# EEZ_PSU_post-regulator_r4B44.net
KiCad netlist of a schematic drawn in EAGLE
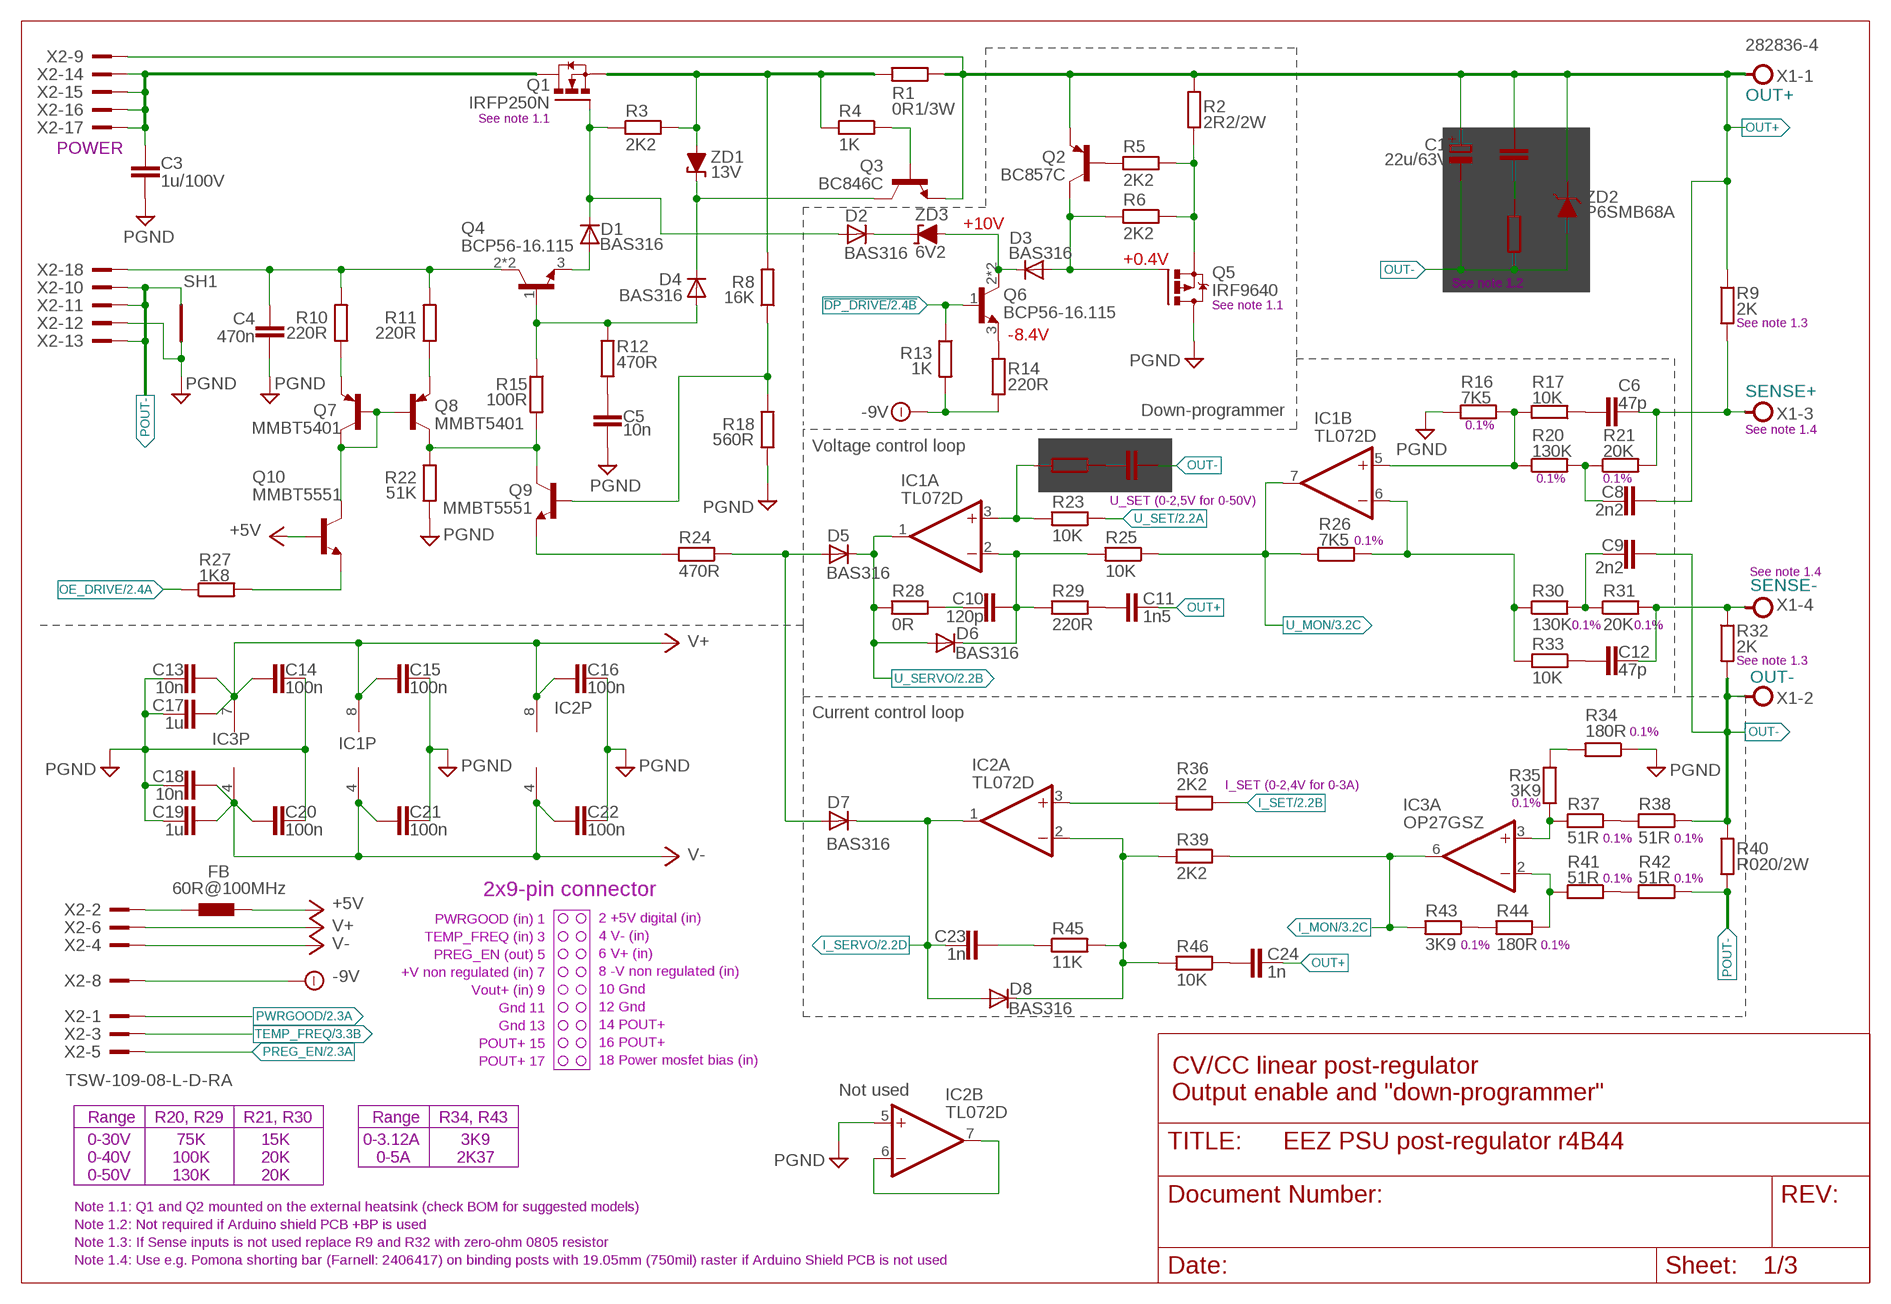
[diagram p0: schematic, sheet 1]
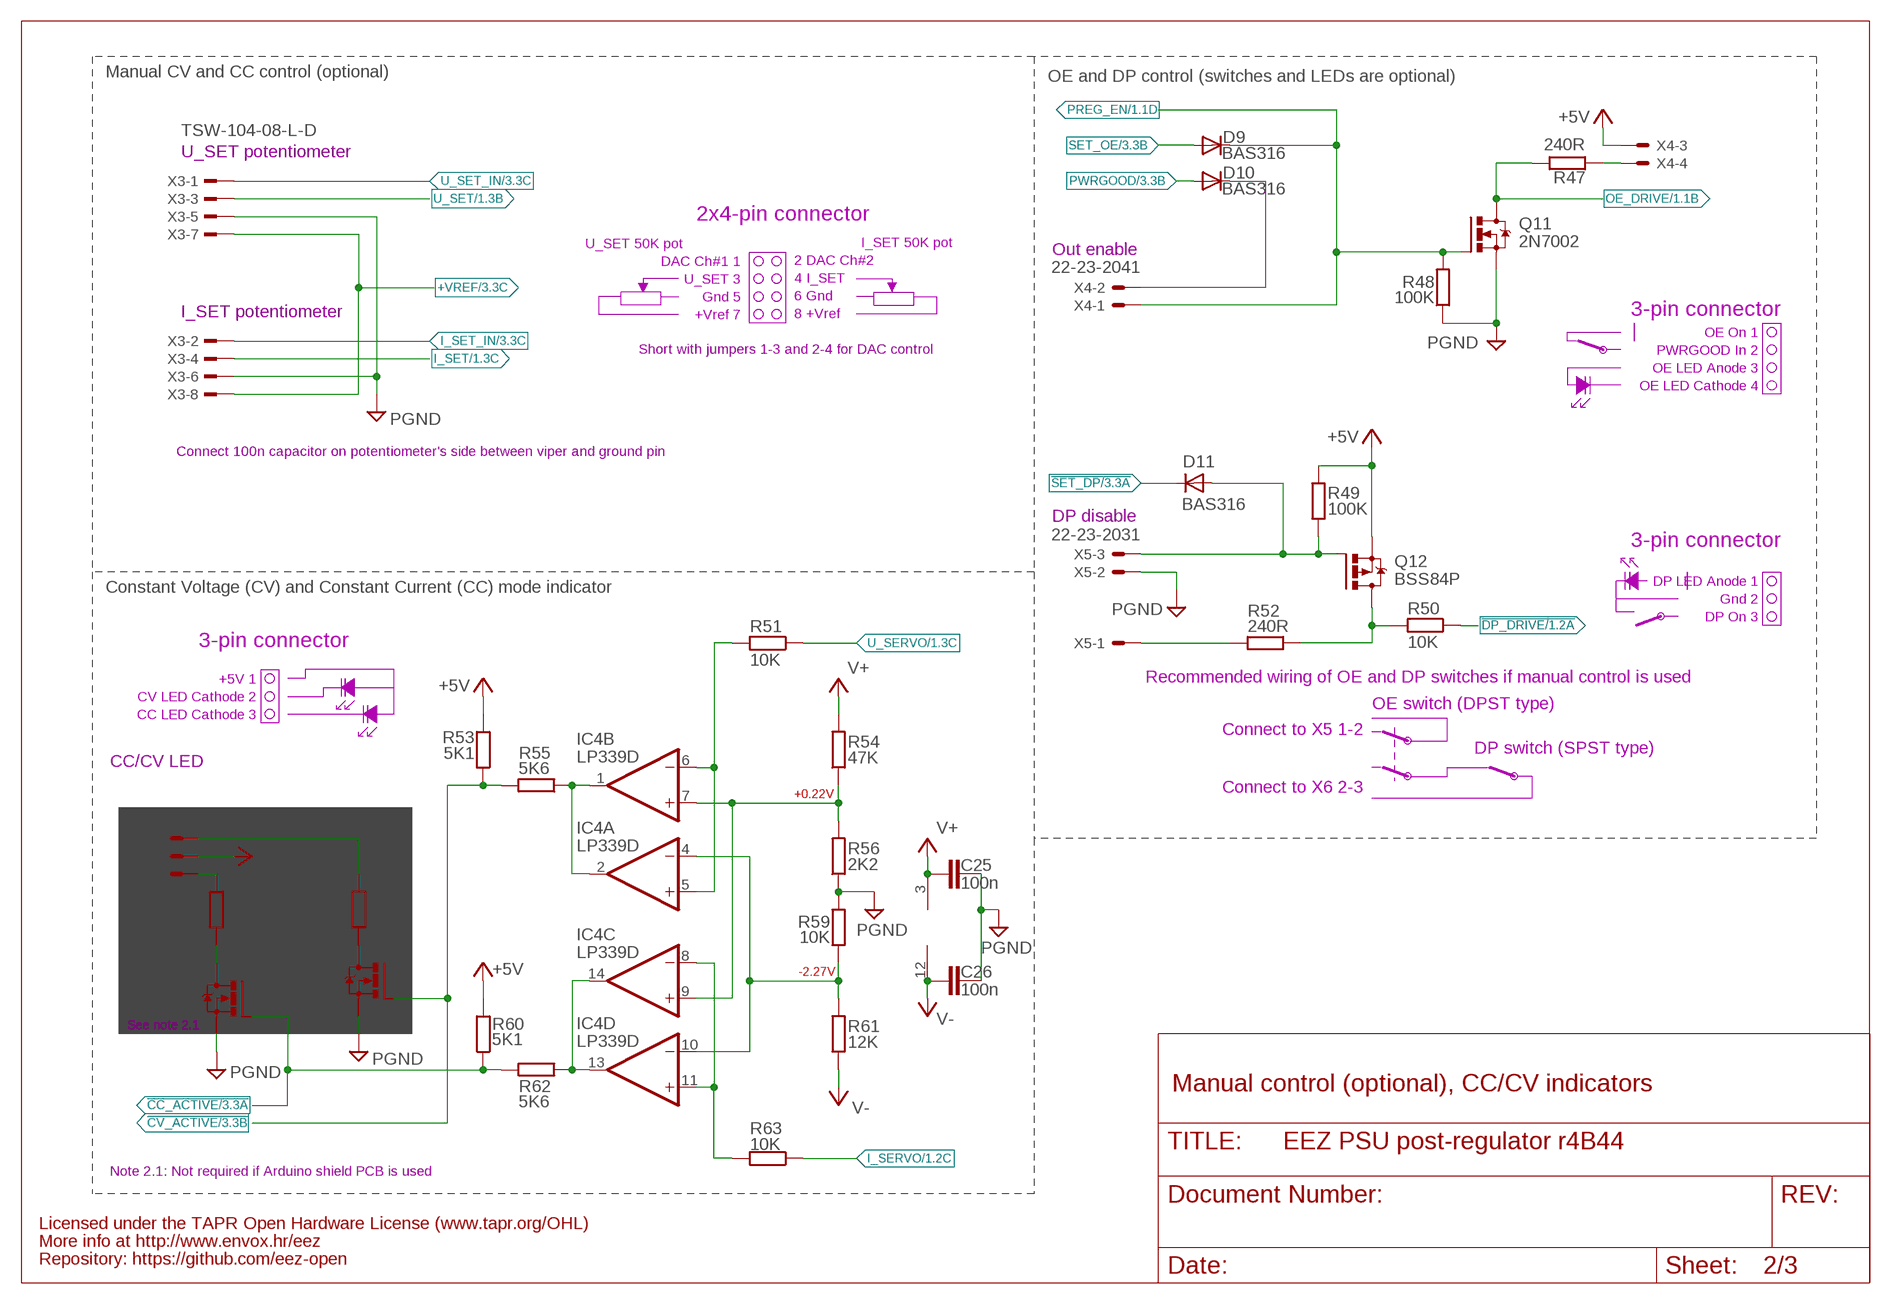
[diagram p1: schematic, sheet 2]
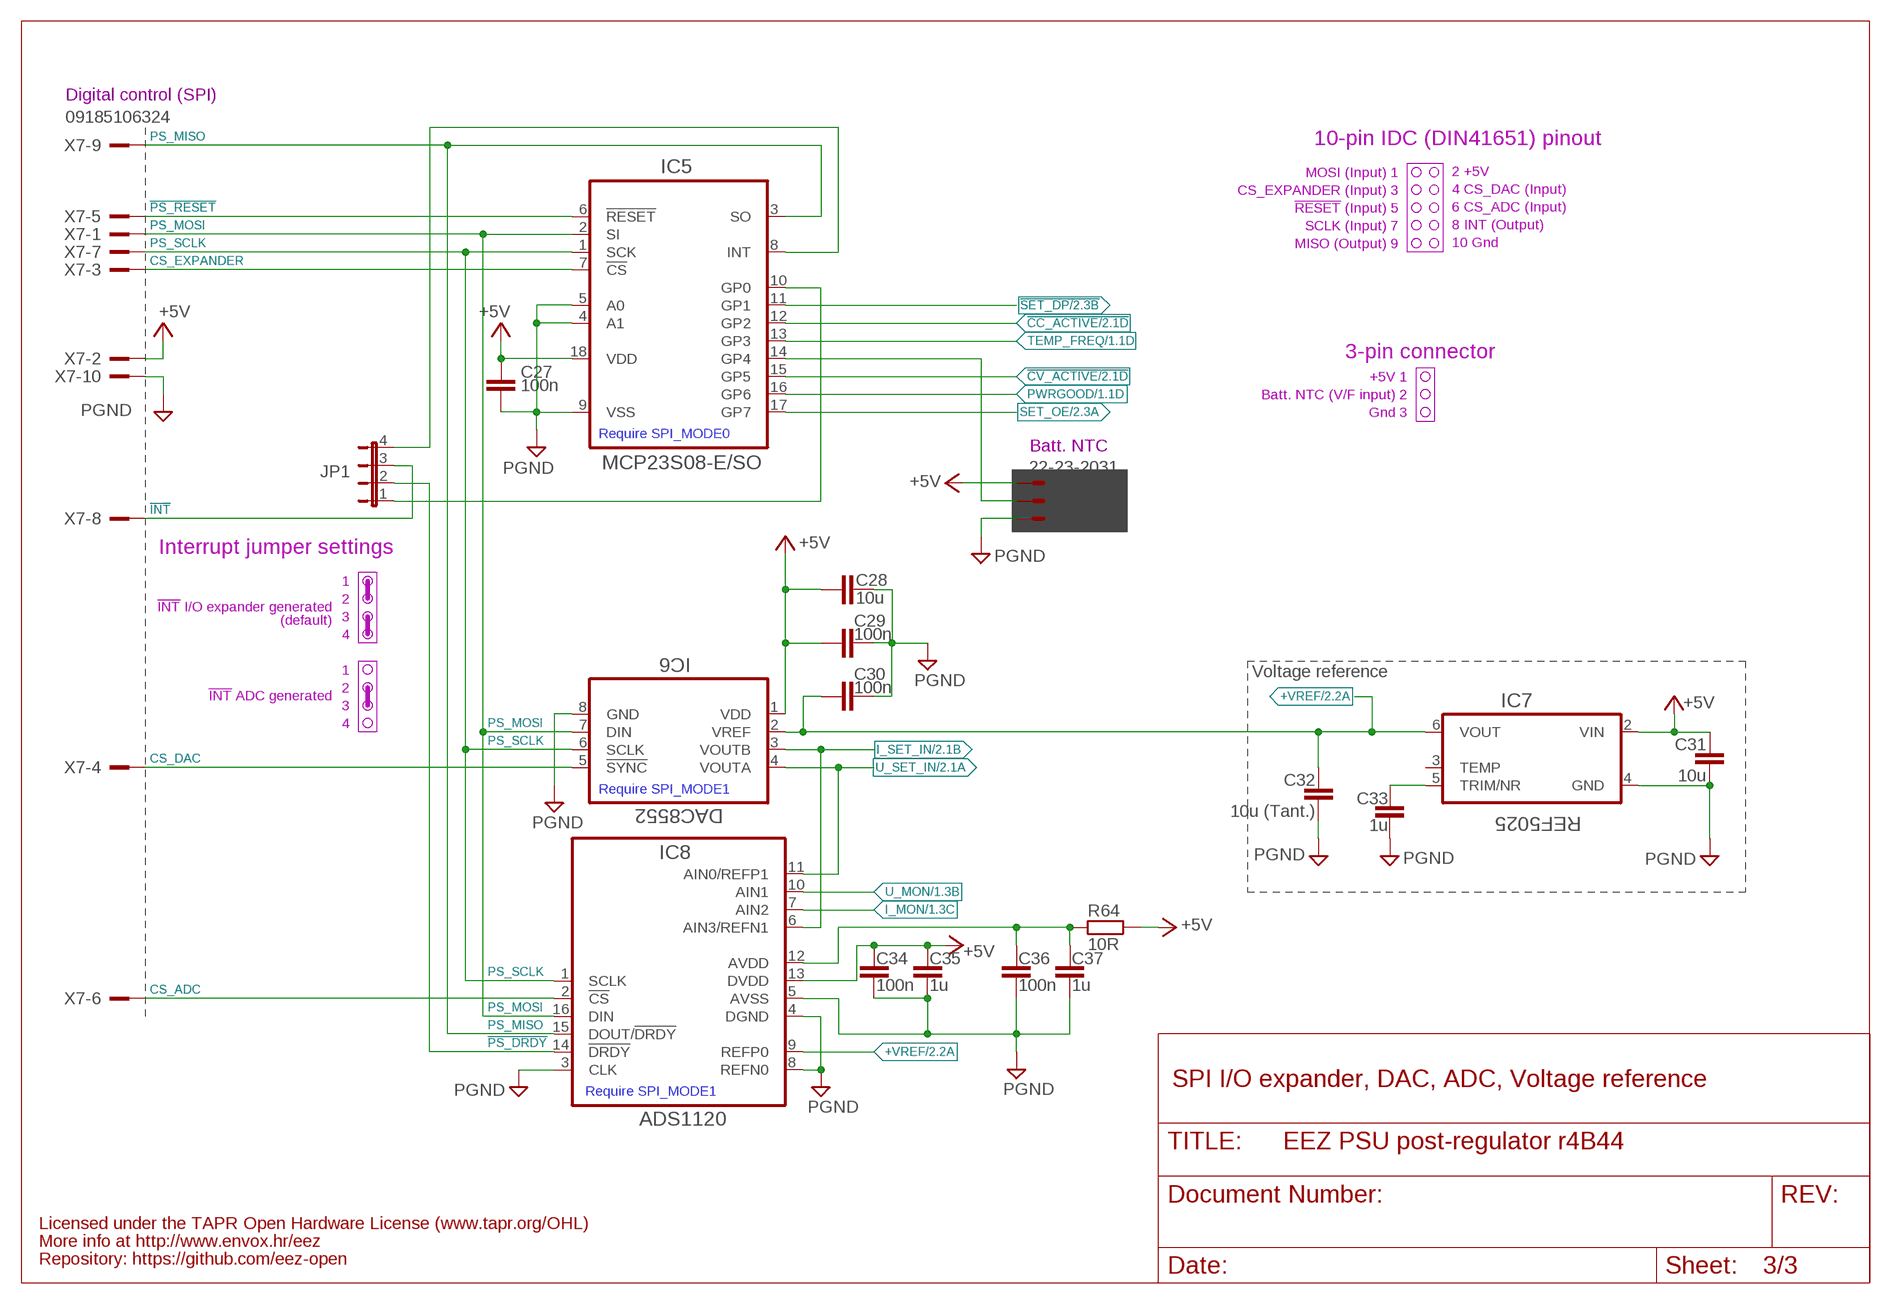
[diagram p2: schematic, sheet 3]

(export (version "E")
  (design (tool "Eeschema 10.0.6"))
  (components
    (comp (ref "C25")
      (value "100n")
      (footprint "eagle-import:C0603")
      (libsource (lib "eagle-import") (part "C-EUC0603"))
    )
    (comp (ref "C26")
      (value "100n")
      (footprint "eagle-import:C0603")
      (libsource (lib "eagle-import") (part "C-EUC0603"))
    )
    (comp (ref "D9")
      (value "BAS316")
      (footprint "eagle-import:SOD323-W")
      (libsource (lib "eagle-import") (part "DIODE-SOD323-W"))
    )
    (comp (ref "D10")
      (value "BAS316")
      (footprint "eagle-import:SOD323-W")
      (libsource (lib "eagle-import") (part "DIODE-SOD323-W"))
    )
    (comp (ref "D11")
      (value "BAS316")
      (footprint "eagle-import:SOD323-W")
      (libsource (lib "eagle-import") (part "DIODE-SOD323-W"))
    )
    (comp (ref "IC4")
      (value "LP339D")
      (footprint "eagle-import:SO14")
      (libsource (lib "eagle-import") (part "LM339D"))
    )
    (comp (ref "Q11")
      (value "2N7002")
      (footprint "eagle-import:SOT103P240X110-3N")
      (fields
        (field (name "MPN") "2N7002-7-F")
        (field (name "MPN_1") "2N7002-7-F")
        (field (name "OC_FARNELL") "1713823")
        (field (name "OC_NEWARK") "25R5679")
        (field (name "PACKAGE") "SOT-23-3")
        (field (name "SUPPLIER") "DIODES INC.")
      )
      (libsource (lib "eagle-import") (part "2N7002"))
    )
    (comp (ref "Q12")
      (value "BSS84P")
      (footprint "eagle-import:SOT95P237X112-3N")
      (fields (field (name "MPN") "IRLML2246TRPBF"))
      (libsource (lib "eagle-import") (part "IRLML2246TRPBF"))
    )
    (comp (ref "Q13")
      (value "2N7002")
      (footprint "eagle-import:SOT103P240X110-3N")
      (fields (field (name "MPN") "2N7002-7-F"))
      (libsource (lib "eagle-import") (part "2N7002"))
    )
    (comp (ref "Q14")
      (value "2N7002")
      (footprint "eagle-import:SOT103P240X110-3N")
      (fields (field (name "MPN") "2N7002-7-F"))
      (libsource (lib "eagle-import") (part "2N7002"))
    )
    (comp (ref "R47")
      (value "240R")
      (footprint "eagle-import:R0805")
      (libsource (lib "eagle-import") (part "R-EU_R0805"))
    )
    (comp (ref "R48")
      (value "100K")
      (footprint "eagle-import:R0805")
      (libsource (lib "eagle-import") (part "R-EU_R0805"))
    )
    (comp (ref "R49")
      (value "100K")
      (footprint "eagle-import:R0805")
      (libsource (lib "eagle-import") (part "R-EU_R0805"))
    )
    (comp (ref "R50")
      (value "10K")
      (footprint "eagle-import:R0805")
      (libsource (lib "eagle-import") (part "R-EU_R0805"))
    )
    (comp (ref "R51")
      (value "10K")
      (footprint "eagle-import:R0805")
      (libsource (lib "eagle-import") (part "R-EU_R0805"))
    )
    (comp (ref "R52")
      (value "240R")
      (footprint "eagle-import:R0805")
      (libsource (lib "eagle-import") (part "R-EU_R0805"))
    )
    (comp (ref "R53")
      (value "5K1")
      (footprint "eagle-import:R0805")
      (libsource (lib "eagle-import") (part "R-EU_R0805"))
    )
    (comp (ref "R54")
      (value "47K")
      (footprint "eagle-import:R0805")
      (libsource (lib "eagle-import") (part "R-EU_R0805"))
    )
    (comp (ref "R55")
      (value "5K6")
      (footprint "eagle-import:R0805")
      (libsource (lib "eagle-import") (part "R-EU_R0805"))
    )
    (comp (ref "R56")
      (value "2K2")
      (footprint "eagle-import:R0805")
      (libsource (lib "eagle-import") (part "R-EU_R0805"))
    )
    (comp (ref "R57")
      (value "240R")
      (footprint "eagle-import:R0805")
      (libsource (lib "eagle-import") (part "R-EU_R0805"))
    )
    (comp (ref "R58")
      (value "240R")
      (footprint "eagle-import:R0805")
      (libsource (lib "eagle-import") (part "R-EU_R0805"))
    )
    (comp (ref "R59")
      (value "10K")
      (footprint "eagle-import:R0805")
      (libsource (lib "eagle-import") (part "R-EU_R0805"))
    )
    (comp (ref "R60")
      (value "5K1")
      (footprint "eagle-import:R0805")
      (libsource (lib "eagle-import") (part "R-EU_R0805"))
    )
    (comp (ref "R61")
      (value "12K")
      (footprint "eagle-import:R0805")
      (libsource (lib "eagle-import") (part "R-EU_R0805"))
    )
    (comp (ref "R62")
      (value "5K6")
      (footprint "eagle-import:R0805")
      (libsource (lib "eagle-import") (part "R-EU_R0805"))
    )
    (comp (ref "R63")
      (value "10K")
      (footprint "eagle-import:R0805")
      (libsource (lib "eagle-import") (part "R-EU_R0805"))
    )
    (comp (ref "X3")
      (value "TSW-104-08-L-D")
      (footprint "eagle-import:TSW-104-02-S-D")
      (libsource (lib "eagle-import") (part "TSW-104-02-S-D"))
    )
    (comp (ref "X4")
      (value "22-23-2041")
      (footprint "eagle-import:22-23-2041")
      (fields
        (field (name "MF") "MOLEX")
        (field (name "MPN") "22-23-2041")
        (field (name "OC_FARNELL") "1462920")
        (field (name "OC_NEWARK") "38C0355")
      )
      (libsource (lib "eagle-import") (part "22-23-2041"))
    )
    (comp (ref "X5")
      (value "22-23-2031")
      (footprint "eagle-import:22-23-2031")
      (fields
        (field (name "MF") "MOLEX")
        (field (name "MF_1") "MOLEX")
        (field (name "MPN") "22-23-2031")
        (field (name "OC_FARNELL") "1462950")
        (field (name "OC_NEWARK") "30C0862")
      )
      (libsource (lib "eagle-import") (part "22-23-2031"))
    )
    (comp (ref "X6")
      (value "22-23-2031")
      (footprint "eagle-import:22-23-2031")
      (fields
        (field (name "MF") "MOLEX")
        (field (name "MPN") "22-23-2031")
        (field (name "OC_FARNELL") "1462950")
        (field (name "OC_NEWARK") "30C0862")
      )
      (libsource (lib "eagle-import") (part "22-23-2031"))
    )
    (comp (ref "C1")
      (value "22u/63V")
      (footprint "eagle-import:CAPAE660X610N_COMBO2")
      (libsource (lib "eagle-import") (part "ECAPEEEFK+2.5MM"))
    )
    (comp (ref "C2")
      (value "470n")
      (footprint "eagle-import:C1812")
      (libsource (lib "eagle-import") (part "C-EUC1812"))
    )
    (comp (ref "C3")
      (value "1u/100V")
      (footprint "eagle-import:C1206")
      (libsource (lib "eagle-import") (part "C-EUC1206"))
    )
    (comp (ref "C4")
      (value "470n")
      (footprint "eagle-import:C1812")
      (libsource (lib "eagle-import") (part "C-EUC1812"))
    )
    (comp (ref "C5")
      (value "10n")
      (footprint "eagle-import:C0805")
      (libsource (lib "eagle-import") (part "C-EUC0805"))
    )
    (comp (ref "C6")
      (value "47p")
      (footprint "eagle-import:C0805")
      (libsource (lib "eagle-import") (part "C-EUC0805"))
    )
    (comp (ref "C7")
      (value "1n5")
      (footprint "eagle-import:C0805")
      (libsource (lib "eagle-import") (part "C-EUC0805"))
    )
    (comp (ref "C8")
      (value "2n2")
      (footprint "eagle-import:C0805")
      (libsource (lib "eagle-import") (part "C-EUC0805"))
    )
    (comp (ref "C9")
      (value "2n2")
      (footprint "eagle-import:C0805")
      (libsource (lib "eagle-import") (part "C-EUC0805"))
    )
    (comp (ref "C10")
      (value "120p")
      (footprint "eagle-import:C0805")
      (libsource (lib "eagle-import") (part "C-EUC0805"))
    )
    (comp (ref "C11")
      (value "1n5")
      (footprint "eagle-import:C0805")
      (libsource (lib "eagle-import") (part "C-EUC0805"))
    )
    (comp (ref "C12")
      (value "47p")
      (footprint "eagle-import:C0805")
      (libsource (lib "eagle-import") (part "C-EUC0805"))
    )
    (comp (ref "C13")
      (value "10n")
      (footprint "eagle-import:C0805")
      (libsource (lib "eagle-import") (part "C-EUC0805"))
    )
    (comp (ref "C14")
      (value "100n")
      (footprint "eagle-import:C0603")
      (libsource (lib "eagle-import") (part "C-EUC0603"))
    )
    (comp (ref "C15")
      (value "100n")
      (footprint "eagle-import:C0603")
      (libsource (lib "eagle-import") (part "C-EUC0603"))
    )
    (comp (ref "C16")
      (value "100n")
      (footprint "eagle-import:C0603")
      (libsource (lib "eagle-import") (part "C-EUC0603"))
    )
    (comp (ref "C17")
      (value "1u")
      (footprint "eagle-import:C0805")
      (libsource (lib "eagle-import") (part "C-EUC0805"))
    )
    (comp (ref "C18")
      (value "10n")
      (footprint "eagle-import:C0805")
      (libsource (lib "eagle-import") (part "C-EUC0805"))
    )
    (comp (ref "C19")
      (value "1u")
      (footprint "eagle-import:C0805")
      (libsource (lib "eagle-import") (part "C-EUC0805"))
    )
    (comp (ref "C20")
      (value "100n")
      (footprint "eagle-import:C0603")
      (libsource (lib "eagle-import") (part "C-EUC0603"))
    )
    (comp (ref "C21")
      (value "100n")
      (footprint "eagle-import:C0603")
      (libsource (lib "eagle-import") (part "C-EUC0603"))
    )
    (comp (ref "C22")
      (value "100n")
      (footprint "eagle-import:C0603")
      (libsource (lib "eagle-import") (part "C-EUC0603"))
    )
    (comp (ref "C23")
      (value "1n")
      (footprint "eagle-import:C0805")
      (libsource (lib "eagle-import") (part "C-EUC0805"))
    )
    (comp (ref "C24")
      (value "1n")
      (footprint "eagle-import:C0805")
      (libsource (lib "eagle-import") (part "C-EUC0805"))
    )
    (comp (ref "D1")
      (value "BAS316")
      (footprint "eagle-import:SOD323-W")
      (libsource (lib "eagle-import") (part "DIODE-SOD323-W"))
    )
    (comp (ref "D2")
      (value "BAS316")
      (footprint "eagle-import:SOD323-W")
      (libsource (lib "eagle-import") (part "DIODE-SOD323-W"))
    )
    (comp (ref "D3")
      (value "BAS316")
      (footprint "eagle-import:SOD323-W")
      (libsource (lib "eagle-import") (part "DIODE-SOD323-W"))
    )
    (comp (ref "D4")
      (value "BAS316")
      (footprint "eagle-import:SOD323-W")
      (libsource (lib "eagle-import") (part "DIODE-SOD323-W"))
    )
    (comp (ref "D5")
      (value "BAS316")
      (footprint "eagle-import:SOD323-W")
      (libsource (lib "eagle-import") (part "DIODE-SOD323-W"))
    )
    (comp (ref "D6")
      (value "BAS316")
      (footprint "eagle-import:SOD323-W")
      (libsource (lib "eagle-import") (part "DIODE-SOD323-W"))
    )
    (comp (ref "D7")
      (value "BAS316")
      (footprint "eagle-import:SOD323-W")
      (libsource (lib "eagle-import") (part "DIODE-SOD323-W"))
    )
    (comp (ref "D8")
      (value "BAS316")
      (footprint "eagle-import:SOD323-W")
      (libsource (lib "eagle-import") (part "DIODE-SOD323-W"))
    )
    (comp (ref "FB")
      (value "60R@100MHz")
      (footprint "eagle-import:BEAD0603")
      (libsource (lib "eagle-import") (part "FERRITE_BEAD0603"))
    )
    (comp (ref "IC1")
      (value "TL072D")
      (footprint "eagle-import:SOIC127P600X173-8N")
      (libsource (lib "eagle-import") (part "TL072SOIC8"))
    )
    (comp (ref "IC2")
      (value "TL072D")
      (footprint "eagle-import:SOIC127P600X173-8N")
      (libsource (lib "eagle-import") (part "TL072SOIC8"))
    )
    (comp (ref "IC3")
      (value "OP27GSZ")
      (footprint "eagle-import:SOIC127P600X173-8N")
      (libsource (lib "eagle-import") (part "OP27GSZSO8"))
    )
    (comp (ref "Q1")
      (value "IRFP250N")
      (footprint "eagle-import:TO247BV")
      (libsource (lib "eagle-import") (part "IRFP240"))
    )
    (comp (ref "Q2")
      (value "BC857C")
      (footprint "eagle-import:SOT23-BEC")
      (libsource (lib "eagle-import") (part "-PNP-SOT23-BECBC857C"))
    )
    (comp (ref "Q3")
      (value "BC846C")
      (footprint "eagle-import:SOT23-BEC")
      (libsource (lib "eagle-import") (part "-NPN-SOT23-BECBC846B"))
    )
    (comp (ref "Q4")
      (value "BCP56-16.115")
      (footprint "eagle-import:SOT230P700X180-4N")
      (libsource (lib "eagle-import") (part "BCP56"))
    )
    (comp (ref "Q5")
      (value "IRF9640")
      (footprint "eagle-import:TO220B-VMOS")
      (libsource (lib "eagle-import") (part "IRF9640"))
    )
    (comp (ref "Q6")
      (value "BCP56-16.115")
      (footprint "eagle-import:SOT230P700X180-4N")
      (libsource (lib "eagle-import") (part "BCP56"))
    )
    (comp (ref "Q7")
      (value "MMBT5401")
      (footprint "eagle-import:SOT23-BEC")
      (libsource (lib "eagle-import") (part "-PNP-SOT23-BECBC857B"))
    )
    (comp (ref "Q8")
      (value "MMBT5401")
      (footprint "eagle-import:SOT23-BEC")
      (libsource (lib "eagle-import") (part "-PNP-SOT23-BECBC857B"))
    )
    (comp (ref "Q9")
      (value "MMBT5551")
      (footprint "eagle-import:SOT23-BEC")
      (libsource (lib "eagle-import") (part "-NPN-SOT23-BECMMBT5551LT1"))
    )
    (comp (ref "Q10")
      (value "MMBT5551")
      (footprint "eagle-import:SOT23-BEC")
      (libsource (lib "eagle-import") (part "-NPN-SOT23-BECMMBT5551LT1"))
    )
    (comp (ref "R1")
      (value "0R1/3W")
      (footprint "eagle-import:0411V")
      (libsource (lib "eagle-import") (part "R-EU_0411/3V"))
    )
    (comp (ref "R2")
      (value "2R2/2W")
      (footprint "eagle-import:0411V")
      (libsource (lib "eagle-import") (part "R-EU_0411/3V"))
    )
    (comp (ref "R3")
      (value "2K2")
      (footprint "eagle-import:R0805")
      (libsource (lib "eagle-import") (part "R-EU_R0805"))
    )
    (comp (ref "R4")
      (value "1K")
      (footprint "eagle-import:R0805")
      (libsource (lib "eagle-import") (part "R-EU_R0805"))
    )
    (comp (ref "R5")
      (value "2K2")
      (footprint "eagle-import:R0805")
      (libsource (lib "eagle-import") (part "R-EU_R0805"))
    )
    (comp (ref "R6")
      (value "2K2")
      (footprint "eagle-import:R0805")
      (libsource (lib "eagle-import") (part "R-EU_R0805"))
    )
    (comp (ref "R7")
      (value "1R")
      (footprint "eagle-import:R0805")
      (libsource (lib "eagle-import") (part "R-EU_R0805"))
    )
    (comp (ref "R8")
      (value "16K")
      (footprint "eagle-import:R0805")
      (libsource (lib "eagle-import") (part "R-EU_R0805"))
    )
    (comp (ref "R9")
      (value "2K")
      (footprint "eagle-import:R0805")
      (libsource (lib "eagle-import") (part "R-EU_R0805"))
    )
    (comp (ref "R10")
      (value "220R")
      (footprint "eagle-import:R0805")
      (libsource (lib "eagle-import") (part "R-EU_R0805"))
    )
    (comp (ref "R11")
      (value "220R")
      (footprint "eagle-import:R0805")
      (libsource (lib "eagle-import") (part "R-EU_R0805"))
    )
    (comp (ref "R12")
      (value "470R")
      (footprint "eagle-import:R0805")
      (libsource (lib "eagle-import") (part "R-EU_R0805"))
    )
    (comp (ref "R13")
      (value "1K")
      (footprint "eagle-import:R0805")
      (libsource (lib "eagle-import") (part "R-EU_R0805"))
    )
    (comp (ref "R14")
      (value "220R")
      (footprint "eagle-import:R0805")
      (libsource (lib "eagle-import") (part "R-EU_R0805"))
    )
    (comp (ref "R15")
      (value "100R")
      (footprint "eagle-import:R0805")
      (libsource (lib "eagle-import") (part "R-EU_R0805"))
    )
    (comp (ref "R16")
      (value "7K5")
      (footprint "eagle-import:R0805")
      (libsource (lib "eagle-import") (part "R-EU_R0805"))
    )
    (comp (ref "R17")
      (value "10K")
      (footprint "eagle-import:R0805")
      (libsource (lib "eagle-import") (part "R-EU_R0805"))
    )
    (comp (ref "R18")
      (value "560R")
      (footprint "eagle-import:R0805")
      (libsource (lib "eagle-import") (part "R-EU_R0805"))
    )
    (comp (ref "R19")
      (value "220R")
      (footprint "eagle-import:R0805")
      (libsource (lib "eagle-import") (part "R-EU_R0805"))
    )
    (comp (ref "R20")
      (value "130K")
      (footprint "eagle-import:R0805")
      (libsource (lib "eagle-import") (part "R-EU_R0805"))
    )
    (comp (ref "R21")
      (value "20K")
      (footprint "eagle-import:R0805")
      (libsource (lib "eagle-import") (part "R-EU_R0805"))
    )
    (comp (ref "R22")
      (value "51K")
      (footprint "eagle-import:R0805")
      (libsource (lib "eagle-import") (part "R-EU_R0805"))
    )
    (comp (ref "R23")
      (value "10K")
      (footprint "eagle-import:R0805")
      (libsource (lib "eagle-import") (part "R-EU_R0805"))
    )
    (comp (ref "R24")
      (value "470R")
      (footprint "eagle-import:R0805")
      (libsource (lib "eagle-import") (part "R-EU_R0805"))
    )
    (comp (ref "R25")
      (value "10K")
      (footprint "eagle-import:R0805")
      (libsource (lib "eagle-import") (part "R-EU_R0805"))
    )
    (comp (ref "R26")
      (value "7K5")
      (footprint "eagle-import:R0805")
      (libsource (lib "eagle-import") (part "R-EU_R0805"))
    )
    (comp (ref "R27")
      (value "1K8")
      (footprint "eagle-import:R0805")
      (libsource (lib "eagle-import") (part "R-EU_R0805"))
    )
    (comp (ref "R28")
      (value "0R")
      (footprint "eagle-import:R0805")
      (libsource (lib "eagle-import") (part "R-EU_R0805"))
    )
    (comp (ref "R29")
      (value "220R")
      (footprint "eagle-import:R0805")
      (libsource (lib "eagle-import") (part "R-EU_R0805"))
    )
    (comp (ref "R30")
      (value "130K")
      (footprint "eagle-import:R0805")
      (libsource (lib "eagle-import") (part "R-EU_R0805"))
    )
    (comp (ref "R31")
      (value "20K")
      (footprint "eagle-import:R0805")
      (libsource (lib "eagle-import") (part "R-EU_R0805"))
    )
    (comp (ref "R32")
      (value "2K")
      (footprint "eagle-import:R0805")
      (libsource (lib "eagle-import") (part "R-EU_R0805"))
    )
    (comp (ref "R33")
      (value "10K")
      (footprint "eagle-import:R0805")
      (libsource (lib "eagle-import") (part "R-EU_R0805"))
    )
    (comp (ref "R34")
      (value "180R")
      (footprint "eagle-import:R0805")
      (libsource (lib "eagle-import") (part "R-EU_R0805"))
    )
    (comp (ref "R35")
      (value "3K9")
      (footprint "eagle-import:R0805")
      (libsource (lib "eagle-import") (part "R-EU_R0805"))
    )
    (comp (ref "R36")
      (value "2K2")
      (footprint "eagle-import:R0805")
      (libsource (lib "eagle-import") (part "R-EU_R0805"))
    )
    (comp (ref "R37")
      (value "51R")
      (footprint "eagle-import:R0805")
      (libsource (lib "eagle-import") (part "R-EU_R0805"))
    )
    (comp (ref "R38")
      (value "51R")
      (footprint "eagle-import:R0805")
      (libsource (lib "eagle-import") (part "R-EU_R0805"))
    )
    (comp (ref "R39")
      (value "2K2")
      (footprint "eagle-import:R0805")
      (libsource (lib "eagle-import") (part "R-EU_R0805"))
    )
    (comp (ref "R40")
      (value "R020/2W")
      (footprint "eagle-import:R2512")
      (libsource (lib "eagle-import") (part "R-EU_R2512"))
    )
    (comp (ref "R41")
      (value "51R")
      (footprint "eagle-import:R0805")
      (libsource (lib "eagle-import") (part "R-EU_R0805"))
    )
    (comp (ref "R42")
      (value "51R")
      (footprint "eagle-import:R0805")
      (libsource (lib "eagle-import") (part "R-EU_R0805"))
    )
    (comp (ref "R43")
      (value "3K9")
      (footprint "eagle-import:R0805")
      (libsource (lib "eagle-import") (part "R-EU_R0805"))
    )
    (comp (ref "R44")
      (value "180R")
      (footprint "eagle-import:R0805")
      (libsource (lib "eagle-import") (part "R-EU_R0805"))
    )
    (comp (ref "R45")
      (value "11K")
      (footprint "eagle-import:R0805")
      (libsource (lib "eagle-import") (part "R-EU_R0805"))
    )
    (comp (ref "R46")
      (value "10K")
      (footprint "eagle-import:R0805")
      (libsource (lib "eagle-import") (part "R-EU_R0805"))
    )
    (comp (ref "SH1")
      (value "GND")
      (footprint "eagle-import:SHORT")
      (libsource (lib "eagle-import") (part "SHORT"))
    )
    (comp (ref "X1")
      (value "282836-4")
      (footprint "eagle-import:TBLOCK5.0_4")
      (libsource (lib "eagle-import") (part "TBLOCK5.0_4A"))
    )
    (comp (ref "X2")
      (value "TSW-109-08-L-D-RA")
      (footprint "eagle-import:TSW-109-08-L-D-RA")
      (fields (field (name "FARNELL") "2032801"))
      (libsource (lib "eagle-import") (part "TSW-109-08-L-D-RA"))
    )
    (comp (ref "ZD1")
      (value "13V")
      (footprint "eagle-import:MINIMELF")
      (libsource (lib "eagle-import") (part "ZENER-DIODEMINIMELF"))
    )
    (comp (ref "ZD2")
      (value "P6SMB68A")
      (footprint "eagle-import:DO214AA")
      (libsource (lib "eagle-import") (part "P6SMB68A"))
    )
    (comp (ref "ZD3")
      (value "6V2")
      (footprint "eagle-import:MINIMELF")
      (libsource (lib "eagle-import") (part "ZENER-DIODEMINIMELF"))
    )
    (comp (ref "C27")
      (value "100n")
      (footprint "eagle-import:C0603")
      (libsource (lib "eagle-import") (part "C-EUC0603"))
    )
    (comp (ref "C28")
      (value "10u")
      (footprint "eagle-import:C1206")
      (libsource (lib "eagle-import") (part "C-EUC1206"))
    )
    (comp (ref "C29")
      (value "100n")
      (footprint "eagle-import:C0603")
      (libsource (lib "eagle-import") (part "C-EUC0603"))
    )
    (comp (ref "C30")
      (value "100n")
      (footprint "eagle-import:C0603")
      (libsource (lib "eagle-import") (part "C-EUC0603"))
    )
    (comp (ref "C31")
      (value "10u")
      (footprint "eagle-import:C1206")
      (libsource (lib "eagle-import") (part "C-EUC1206"))
    )
    (comp (ref "C32")
      (value "10u (Tant.)")
      (footprint "eagle-import:C1206")
      (libsource (lib "eagle-import") (part "C-EUC1206"))
    )
    (comp (ref "C33")
      (value "1u")
      (footprint "eagle-import:C0805")
      (libsource (lib "eagle-import") (part "C-EUC0805"))
    )
    (comp (ref "C34")
      (value "100n")
      (footprint "eagle-import:C0603")
      (libsource (lib "eagle-import") (part "C-EUC0603"))
    )
    (comp (ref "C35")
      (value "1u")
      (footprint "eagle-import:C0805")
      (libsource (lib "eagle-import") (part "C-EUC0805"))
    )
    (comp (ref "C36")
      (value "100n")
      (footprint "eagle-import:C0603")
      (libsource (lib "eagle-import") (part "C-EUC0603"))
    )
    (comp (ref "C37")
      (value "1u")
      (footprint "eagle-import:C0805")
      (libsource (lib "eagle-import") (part "C-EUC0805"))
    )
    (comp (ref "IC5")
      (value "MCP23S08-E/SO")
      (footprint "eagle-import:SOIC127P1030X265-18N")
      (libsource (lib "eagle-import") (part "MCP23S08"))
    )
    (comp (ref "IC6")
      (value "DAC8552")
      (footprint "eagle-import:DGK8-M")
      (libsource (lib "eagle-import") (part "DAC8552_DGK_8M"))
    )
    (comp (ref "IC7")
      (value "REF5025")
      (footprint "eagle-import:SOIC127P600X175-8N")
      (libsource (lib "eagle-import") (part "REF50XX"))
    )
    (comp (ref "IC8")
      (value "ADS1120")
      (footprint "eagle-import:PW(R-PDSO-G16)")
      (libsource (lib "eagle-import") (part "ADS1120TSSOP-16"))
    )
    (comp (ref "JP1")
      (value "JP4E")
      (footprint "eagle-import:JP4")
      (libsource (lib "eagle-import") (part "JP4E"))
    )
    (comp (ref "R64")
      (value "10R")
      (footprint "eagle-import:R0805")
      (libsource (lib "eagle-import") (part "R-EU_R0805"))
    )
    (comp (ref "X7")
      (value "09185106324")
      (footprint "eagle-import:PAK100_2500-10")
      (fields (field (name "MF") "3M") (field (name "MPN") "2510-6002UB"))
      (libsource (lib "eagle-import") (part "2510-"))
    )
    (comp (ref "X8")
      (value "22-23-2031")
      (footprint "eagle-import:22-23-2031")
      (fields
        (field (name "MF") "MOLEX")
        (field (name "MPN") "22-23-2031")
        (field (name "OC_FARNELL") "1462950")
        (field (name "OC_NEWARK") "30C0862")
      )
      (libsource (lib "eagle-import") (part "22-23-2031"))
    )
  )
  (nets
    (net (code "1") (name "+5V") (class "Default")
      (node (ref "C27") (pin "1") (pinfunction "1_1") (pintype "passive"))
      (node (ref "C28") (pin "1") (pinfunction "1_1") (pintype "passive"))
      (node (ref "C29") (pin "2") (pinfunction "2_2") (pintype "passive"))
      (node (ref "C31") (pin "1") (pinfunction "1_1") (pintype "passive"))
      (node (ref "C34") (pin "2") (pinfunction "2_2") (pintype "passive"))
      (node (ref "C35") (pin "2") (pinfunction "2_2") (pintype "passive"))
      (node (ref "FB") (pin "P$2") (pinfunction "2_P$2") (pintype "passive"))
      (node (ref "IC5") (pin "18") (pinfunction "VDD_18") (pintype "power_in"))
      (node (ref "IC6") (pin "1") (pinfunction "VDD_1") (pintype "power_in"))
      (node (ref "IC7") (pin "2") (pinfunction "VIN_2") (pintype "passive"))
      (node (ref "IC8") (pin "13") (pinfunction "DVDD_13") (pintype "power_in"))
      (node (ref "Q10") (pin "B") (pinfunction "B_B") (pintype "passive"))
      (node (ref "Q12") (pin "2") (pinfunction "S_2") (pintype "passive"))
      (node (ref "R49") (pin "1") (pinfunction "1_1") (pintype "passive"))
      (node (ref "R53") (pin "2") (pinfunction "2_2") (pintype "passive"))
      (node (ref "R60") (pin "2") (pinfunction "2_2") (pintype "passive"))
      (node (ref "R64") (pin "1") (pinfunction "1_1") (pintype "passive"))
      (node (ref "X4") (pin "3") (pinfunction "S_3") (pintype "passive"))
      (node (ref "X6") (pin "2") (pinfunction "S_2") (pintype "passive"))
      (node (ref "X7") (pin "2") (pinfunction "KL_2") (pintype "passive"))
      (node (ref "X8") (pin "1") (pinfunction "S_1") (pintype "passive"))
    )
    (net (code "2") (name "+VREF") (class "Default")
      (node (ref "C30") (pin "2") (pinfunction "2_2") (pintype "passive"))
      (node (ref "C32") (pin "1") (pinfunction "1_1") (pintype "passive"))
      (node (ref "IC6") (pin "2") (pinfunction "VREF_2") (pintype "input"))
      (node (ref "IC7") (pin "6") (pinfunction "VOUT_6") (pintype "output"))
      (node (ref "IC8") (pin "9") (pinfunction "REFP0_9") (pintype "input"))
      (node (ref "X3") (pin "7") (pinfunction "1_7") (pintype "passive"))
      (node (ref "X3") (pin "8") (pinfunction "1_8") (pintype "passive"))
    )
    (net (code "3") (name "-9V") (class "Default")
      (node (ref "R13") (pin "2") (pinfunction "2_2") (pintype "passive"))
      (node (ref "R14") (pin "2") (pinfunction "2_2") (pintype "passive"))
      (node (ref "X2") (pin "8") (pinfunction "KL_8") (pintype "passive"))
    )
    (net (code "4") (name "CS_ADC") (class "Default")
      (node (ref "IC8") (pin "2") (pinfunction "~{CS}_2") (pintype "input"))
      (node (ref "X7") (pin "6") (pinfunction "KL_6") (pintype "passive"))
    )
    (net (code "5") (name "CS_DAC") (class "Default")
      (node (ref "IC6") (pin "5") (pinfunction "~{SYNC}_5") (pintype "input"))
      (node (ref "X7") (pin "4") (pinfunction "KL_4") (pintype "passive"))
    )
    (net (code "6") (name "CS_EXPANDER") (class "Default")
      (node (ref "IC5") (pin "7") (pinfunction "~{CS}_7") (pintype "input"))
      (node (ref "X7") (pin "3") (pinfunction "KL_3") (pintype "passive"))
    )
    (net (code "7") (name "GND") (class "Default")
      (node (ref "C13") (pin "1") (pinfunction "1_1") (pintype "passive"))
      (node (ref "C14") (pin "2") (pinfunction "2_2") (pintype "passive"))
      (node (ref "C15") (pin "1") (pinfunction "1_1") (pintype "passive"))
      (node (ref "C16") (pin "1") (pinfunction "1_1") (pintype "passive"))
      (node (ref "C17") (pin "1") (pinfunction "1_1") (pintype "passive"))
      (node (ref "C18") (pin "1") (pinfunction "1_1") (pintype "passive"))
      (node (ref "C19") (pin "1") (pinfunction "1_1") (pintype "passive"))
      (node (ref "C20") (pin "2") (pinfunction "2_2") (pintype "passive"))
      (node (ref "C21") (pin "1") (pinfunction "1_1") (pintype "passive"))
      (node (ref "C22") (pin "1") (pinfunction "1_1") (pintype "passive"))
      (node (ref "C25") (pin "1") (pinfunction "1_1") (pintype "passive"))
      (node (ref "C26") (pin "1") (pinfunction "1_1") (pintype "passive"))
      (node (ref "C27") (pin "2") (pinfunction "2_2") (pintype "passive"))
      (node (ref "C28") (pin "2") (pinfunction "2_2") (pintype "passive"))
      (node (ref "C29") (pin "1") (pinfunction "1_1") (pintype "passive"))
      (node (ref "C3") (pin "2") (pinfunction "2_2") (pintype "passive"))
      (node (ref "C30") (pin "1") (pinfunction "1_1") (pintype "passive"))
      (node (ref "C31") (pin "2") (pinfunction "2_2") (pintype "passive"))
      (node (ref "C32") (pin "2") (pinfunction "2_2") (pintype "passive"))
      (node (ref "C33") (pin "2") (pinfunction "2_2") (pintype "passive"))
      (node (ref "C34") (pin "1") (pinfunction "1_1") (pintype "passive"))
      (node (ref "C35") (pin "1") (pinfunction "1_1") (pintype "passive"))
      (node (ref "C36") (pin "1") (pinfunction "1_1") (pintype "passive"))
      (node (ref "C37") (pin "1") (pinfunction "1_1") (pintype "passive"))
      (node (ref "C4") (pin "2") (pinfunction "2_2") (pintype "passive"))
      (node (ref "C5") (pin "2") (pinfunction "2_2") (pintype "passive"))
      (node (ref "IC2") (pin "5") (pinfunction "+IN_5") (pintype "input"))
      (node (ref "IC5") (pin "4") (pinfunction "A1_4") (pintype "input"))
      (node (ref "IC5") (pin "5") (pinfunction "A0_5") (pintype "input"))
      (node (ref "IC5") (pin "9") (pinfunction "VSS_9") (pintype "power_in"))
      (node (ref "IC6") (pin "8") (pinfunction "GND_8") (pintype "power_in"))
      (node (ref "IC7") (pin "4") (pinfunction "GND_4") (pintype "passive"))
      (node (ref "IC8") (pin "3") (pinfunction "CLK_3") (pintype "bidirectional"))
      (node (ref "IC8") (pin "4") (pinfunction "DGND_4") (pintype "power_in"))
      (node (ref "IC8") (pin "5") (pinfunction "AVSS_5") (pintype "power_in"))
      (node (ref "IC8") (pin "8") (pinfunction "REFN0_8") (pintype "input"))
      (node (ref "Q11") (pin "2") (pinfunction "S_2") (pintype "passive"))
      (node (ref "Q13") (pin "2") (pinfunction "S_2") (pintype "passive"))
      (node (ref "Q14") (pin "2") (pinfunction "S_2") (pintype "passive"))
      (node (ref "Q5") (pin "D") (pinfunction "D_D") (pintype "passive"))
      (node (ref "R16") (pin "1") (pinfunction "1_1") (pintype "passive"))
      (node (ref "R18") (pin "1") (pinfunction "1_1") (pintype "passive"))
      (node (ref "R22") (pin "1") (pinfunction "1_1") (pintype "passive"))
      (node (ref "R34") (pin "1") (pinfunction "1_1") (pintype "passive"))
      (node (ref "R48") (pin "1") (pinfunction "1_1") (pintype "passive"))
      (node (ref "R56") (pin "1") (pinfunction "1_1") (pintype "passive"))
      (node (ref "R59") (pin "2") (pinfunction "2_2") (pintype "passive"))
      (node (ref "SH1") (pin "1") (pinfunction "GND_A_1") (pintype "bidirectional"))
      (node (ref "X2") (pin "12") (pinfunction "KL_12") (pintype "passive"))
      (node (ref "X3") (pin "5") (pinfunction "1_5") (pintype "passive"))
      (node (ref "X3") (pin "6") (pinfunction "1_6") (pintype "passive"))
      (node (ref "X5") (pin "2") (pinfunction "S_2") (pintype "passive"))
      (node (ref "X7") (pin "10") (pinfunction "KL_10") (pintype "passive"))
      (node (ref "X8") (pin "3") (pinfunction "S_3") (pintype "passive"))
    )
    (net (code "8") (name "I_MON") (class "Default")
      (node (ref "IC3") (pin "6") (pinfunction "OUT_6") (pintype "output"))
      (node (ref "IC8") (pin "7") (pinfunction "AIN2_7") (pintype "input"))
      (node (ref "R39") (pin "1") (pinfunction "1_1") (pintype "passive"))
      (node (ref "R43") (pin "2") (pinfunction "2_2") (pintype "passive"))
    )
    (net (code "9") (name "I_SERVO") (class "Default")
      (node (ref "C23") (pin "2") (pinfunction "2_2") (pintype "passive"))
      (node (ref "D7") (pin "C") (pinfunction "C_C") (pintype "passive"))
      (node (ref "D8") (pin "A") (pinfunction "A_A") (pintype "passive"))
      (node (ref "IC2") (pin "1") (pinfunction "OUT_1") (pintype "output"))
      (node (ref "R63") (pin "1") (pinfunction "1_1") (pintype "passive"))
    )
    (net (code "10") (name "I_SET") (class "Default")
      (node (ref "R36") (pin "1") (pinfunction "1_1") (pintype "passive"))
      (node (ref "X3") (pin "4") (pinfunction "1_4") (pintype "passive"))
    )
    (net (code "11") (name "I_SET_IN") (class "Default")
      (node (ref "IC6") (pin "3") (pinfunction "VOUTB_3") (pintype "output"))
      (node (ref "IC8") (pin "6") (pinfunction "AIN3/REFN1_6") (pintype "input"))
      (node (ref "X3") (pin "2") (pinfunction "1_2") (pintype "passive"))
    )
    (net (code "12") (name "Net-(C2-Pad2)") (class "Default")
      (node (ref "C2") (pin "2") (pinfunction "2_2") (pintype "passive"))
      (node (ref "R7") (pin "2") (pinfunction "2_2") (pintype "passive"))
    )
    (net (code "13") (name "Net-(C5-Pad1)") (class "Default")
      (node (ref "C5") (pin "1") (pinfunction "1_1") (pintype "passive"))
      (node (ref "R12") (pin "1") (pinfunction "1_1") (pintype "passive"))
    )
    (net (code "14") (name "Net-(C6-Pad2)") (class "Default")
      (node (ref "C6") (pin "2") (pinfunction "2_2") (pintype "passive"))
      (node (ref "R17") (pin "1") (pinfunction "1_1") (pintype "passive"))
    )
    (net (code "15") (name "Net-(C7-Pad2)") (class "Default")
      (node (ref "C7") (pin "2") (pinfunction "2_2") (pintype "passive"))
      (node (ref "R19") (pin "1") (pinfunction "1_1") (pintype "passive"))
    )
    (net (code "16") (name "Net-(C8-Pad1)") (class "Default")
      (node (ref "C8") (pin "1") (pinfunction "1_1") (pintype "passive"))
      (node (ref "R20") (pin "2") (pinfunction "2_2") (pintype "passive"))
      (node (ref "R21") (pin "1") (pinfunction "1_1") (pintype "passive"))
    )
    (net (code "17") (name "Net-(C9-Pad1)") (class "Default")
      (node (ref "C9") (pin "1") (pinfunction "1_1") (pintype "passive"))
      (node (ref "R30") (pin "2") (pinfunction "2_2") (pintype "passive"))
      (node (ref "R31") (pin "1") (pinfunction "1_1") (pintype "passive"))
    )
    (net (code "18") (name "Net-(C10-Pad2)") (class "Default")
      (node (ref "C10") (pin "2") (pinfunction "2_2") (pintype "passive"))
      (node (ref "R28") (pin "1") (pinfunction "1_1") (pintype "passive"))
    )
    (net (code "19") (name "Net-(C11-Pad2)") (class "Default")
      (node (ref "C11") (pin "2") (pinfunction "2_2") (pintype "passive"))
      (node (ref "R29") (pin "1") (pinfunction "1_1") (pintype "passive"))
    )
    (net (code "20") (name "Net-(C12-Pad2)") (class "Default")
      (node (ref "C12") (pin "2") (pinfunction "2_2") (pintype "passive"))
      (node (ref "R33") (pin "1") (pinfunction "1_1") (pintype "passive"))
    )
    (net (code "21") (name "Net-(C23-Pad1)") (class "Default")
      (node (ref "C23") (pin "1") (pinfunction "1_1") (pintype "passive"))
      (node (ref "R45") (pin "1") (pinfunction "1_1") (pintype "passive"))
    )
    (net (code "22") (name "Net-(C24-Pad2)") (class "Default")
      (node (ref "C24") (pin "2") (pinfunction "2_2") (pintype "passive"))
      (node (ref "R46") (pin "1") (pinfunction "1_1") (pintype "passive"))
    )
    (net (code "23") (name "Net-(D1-PadC)") (class "Default")
      (node (ref "D1") (pin "C") (pinfunction "C_C") (pintype "passive"))
      (node (ref "D2") (pin "A") (pinfunction "A_A") (pintype "passive"))
      (node (ref "Q1") (pin "G") (pinfunction "G_G") (pintype "passive"))
      (node (ref "R3") (pin "1") (pinfunction "1_1") (pintype "passive"))
    )
    (net (code "24") (name "Net-(D2-PadC)") (class "Default")
      (node (ref "D2") (pin "C") (pinfunction "C_C") (pintype "passive"))
      (node (ref "ZD3") (pin "C") (pinfunction "C_C") (pintype "passive"))
    )
    (net (code "25") (name "Net-(D3-PadA)") (class "Default")
      (node (ref "D3") (pin "A") (pinfunction "A_A") (pintype "passive"))
      (node (ref "Q2") (pin "C") (pinfunction "C_C") (pintype "passive"))
      (node (ref "Q5") (pin "G") (pinfunction "G_G") (pintype "passive"))
      (node (ref "R6") (pin "2") (pinfunction "2_2") (pintype "passive"))
    )
    (net (code "26") (name "Net-(D3-PadC)") (class "Default")
      (node (ref "D3") (pin "C") (pinfunction "C_C") (pintype "passive"))
      (node (ref "Q6") (pin "2") (pinfunction "C_2") (pintype "passive"))
      (node (ref "Q6") (pin "4") (pinfunction "C_4") (pintype "passive"))
      (node (ref "ZD3") (pin "A") (pinfunction "A_A") (pintype "passive"))
    )
    (net (code "27") (name "Net-(D4-PadC)") (class "Default")
      (node (ref "D4") (pin "C") (pinfunction "C_C") (pintype "passive"))
      (node (ref "Q3") (pin "C") (pinfunction "C_C") (pintype "passive"))
      (node (ref "ZD1") (pin "C") (pinfunction "C_C") (pintype "passive"))
    )
    (net (code "28") (name "Net-(D5-PadA)") (class "Default")
      (node (ref "D5") (pin "A") (pinfunction "A_A") (pintype "passive"))
      (node (ref "D7") (pin "A") (pinfunction "A_A") (pintype "passive"))
      (node (ref "R24") (pin "1") (pinfunction "1_1") (pintype "passive"))
    )
    (net (code "29") (name "Net-(FB-1)") (class "Default")
      (node (ref "FB") (pin "P$1") (pinfunction "1_P$1") (pintype "passive"))
      (node (ref "X2") (pin "2") (pinfunction "KL_2") (pintype "passive"))
    )
    (net (code "30") (name "Net-(IC1A-+IN)") (class "Default")
      (node (ref "IC1") (pin "3") (pinfunction "+IN_3") (pintype "input"))
      (node (ref "R19") (pin "2") (pinfunction "2_2") (pintype "passive"))
      (node (ref "R23") (pin "2") (pinfunction "2_2") (pintype "passive"))
    )
    (net (code "31") (name "Net-(IC1A--IN)") (class "Default")
      (node (ref "C10") (pin "1") (pinfunction "1_1") (pintype "passive"))
      (node (ref "D6") (pin "C") (pinfunction "C_C") (pintype "passive"))
      (node (ref "IC1") (pin "2") (pinfunction "-IN_2") (pintype "input"))
      (node (ref "R25") (pin "2") (pinfunction "2_2") (pintype "passive"))
      (node (ref "R29") (pin "2") (pinfunction "2_2") (pintype "passive"))
    )
    (net (code "32") (name "Net-(IC1B-+IN)") (class "Default")
      (node (ref "IC1") (pin "5") (pinfunction "+IN_5") (pintype "input"))
      (node (ref "R16") (pin "2") (pinfunction "2_2") (pintype "passive"))
      (node (ref "R17") (pin "2") (pinfunction "2_2") (pintype "passive"))
      (node (ref "R20") (pin "1") (pinfunction "1_1") (pintype "passive"))
    )
    (net (code "33") (name "Net-(IC1B--IN)") (class "Default")
      (node (ref "IC1") (pin "6") (pinfunction "-IN_6") (pintype "input"))
      (node (ref "R26") (pin "2") (pinfunction "2_2") (pintype "passive"))
      (node (ref "R30") (pin "1") (pinfunction "1_1") (pintype "passive"))
      (node (ref "R33") (pin "2") (pinfunction "2_2") (pintype "passive"))
    )
    (net (code "34") (name "Net-(IC2A-+IN)") (class "Default")
      (node (ref "IC2") (pin "3") (pinfunction "+IN_3") (pintype "input"))
      (node (ref "R36") (pin "2") (pinfunction "2_2") (pintype "passive"))
    )
    (net (code "35") (name "Net-(IC2A--IN)") (class "Default")
      (node (ref "D8") (pin "C") (pinfunction "C_C") (pintype "passive"))
      (node (ref "IC2") (pin "2") (pinfunction "-IN_2") (pintype "input"))
      (node (ref "R39") (pin "2") (pinfunction "2_2") (pintype "passive"))
      (node (ref "R45") (pin "2") (pinfunction "2_2") (pintype "passive"))
      (node (ref "R46") (pin "2") (pinfunction "2_2") (pintype "passive"))
    )
    (net (code "36") (name "Net-(IC2B--IN)") (class "Default")
      (node (ref "IC2") (pin "6") (pinfunction "-IN_6") (pintype "input"))
      (node (ref "IC2") (pin "7") (pinfunction "OUT_7") (pintype "output"))
    )
    (net (code "37") (name "Net-(IC3A-+IN)") (class "Default")
      (node (ref "IC3") (pin "3") (pinfunction "+IN_3") (pintype "input"))
      (node (ref "R35") (pin "2") (pinfunction "2_2") (pintype "passive"))
      (node (ref "R37") (pin "2") (pinfunction "2_2") (pintype "passive"))
    )
    (net (code "38") (name "Net-(IC3A--IN)") (class "Default")
      (node (ref "IC3") (pin "2") (pinfunction "-IN_2") (pintype "input"))
      (node (ref "R41") (pin "2") (pinfunction "2_2") (pintype "passive"))
      (node (ref "R44") (pin "1") (pinfunction "1_1") (pintype "passive"))
    )
    (net (code "39") (name "Net-(IC4A-+IN)") (class "Default")
      (node (ref "IC4") (pin "5") (pinfunction "+IN_5") (pintype "input"))
      (node (ref "IC4") (pin "6") (pinfunction "-IN_6") (pintype "input"))
      (node (ref "R51") (pin "2") (pinfunction "2_2") (pintype "passive"))
    )
    (net (code "40") (name "Net-(IC4A--IN)") (class "Default")
      (node (ref "IC4") (pin "10") (pinfunction "-IN_10") (pintype "input"))
      (node (ref "IC4") (pin "4") (pinfunction "-IN_4") (pintype "input"))
      (node (ref "R59") (pin "1") (pinfunction "1_1") (pintype "passive"))
      (node (ref "R61") (pin "2") (pinfunction "2_2") (pintype "passive"))
    )
    (net (code "41") (name "Net-(IC4A-OUT)") (class "Default")
      (node (ref "IC4") (pin "1") (pinfunction "OUT_1") (pintype "open_collector"))
      (node (ref "IC4") (pin "2") (pinfunction "OUT_2") (pintype "open_collector"))
      (node (ref "R55") (pin "1") (pinfunction "1_1") (pintype "passive"))
    )
    (net (code "42") (name "Net-(IC4B-+IN)") (class "Default")
      (node (ref "IC4") (pin "7") (pinfunction "+IN_7") (pintype "input"))
      (node (ref "IC4") (pin "9") (pinfunction "+IN_9") (pintype "input"))
      (node (ref "R54") (pin "1") (pinfunction "1_1") (pintype "passive"))
      (node (ref "R56") (pin "2") (pinfunction "2_2") (pintype "passive"))
    )
    (net (code "43") (name "Net-(IC4C--IN)") (class "Default")
      (node (ref "IC4") (pin "11") (pinfunction "+IN_11") (pintype "input"))
      (node (ref "IC4") (pin "8") (pinfunction "-IN_8") (pintype "input"))
      (node (ref "R63") (pin "2") (pinfunction "2_2") (pintype "passive"))
    )
    (net (code "44") (name "Net-(IC4C-OUT)") (class "Default")
      (node (ref "IC4") (pin "13") (pinfunction "OUT_13") (pintype "open_collector"))
      (node (ref "IC4") (pin "14") (pinfunction "OUT_14") (pintype "open_collector"))
      (node (ref "R62") (pin "1") (pinfunction "1_1") (pintype "passive"))
    )
    (net (code "45") (name "Net-(IC5-GP0)") (class "Default")
      (node (ref "IC5") (pin "10") (pinfunction "GP0_10") (pintype "bidirectional"))
      (node (ref "JP1") (pin "1") (pinfunction "1_1") (pintype "passive"))
    )
    (net (code "46") (name "Net-(IC5-GP4)") (class "Default")
      (node (ref "IC5") (pin "14") (pinfunction "GP4_14") (pintype "bidirectional"))
      (node (ref "X8") (pin "2") (pinfunction "S_2") (pintype "passive"))
    )
    (net (code "47") (name "Net-(IC5-INT)") (class "Default")
      (node (ref "IC5") (pin "8") (pinfunction "INT_8") (pintype "output"))
      (node (ref "JP1") (pin "4") (pinfunction "4_4") (pintype "passive"))
    )
    (net (code "48") (name "Net-(IC7-TRIM{slash}NR)") (class "Default")
      (node (ref "C33") (pin "1") (pinfunction "1_1") (pintype "passive"))
      (node (ref "IC7") (pin "5") (pinfunction "TRIM/NR_5") (pintype "input"))
    )
    (net (code "49") (name "Net-(IC8-AVDD)") (class "Default")
      (node (ref "C36") (pin "2") (pinfunction "2_2") (pintype "passive"))
      (node (ref "C37") (pin "2") (pinfunction "2_2") (pintype "passive"))
      (node (ref "IC8") (pin "12") (pinfunction "AVDD_12") (pintype "power_in"))
      (node (ref "R64") (pin "2") (pinfunction "2_2") (pintype "passive"))
    )
    (net (code "50") (name "Net-(Q1-PadS)") (class "Default")
      (node (ref "Q1") (pin "S") (pinfunction "S_S") (pintype "passive"))
      (node (ref "R1") (pin "2") (pinfunction "2_2") (pintype "passive"))
      (node (ref "R3") (pin "2") (pinfunction "2_2") (pintype "passive"))
      (node (ref "R4") (pin "2") (pinfunction "2_2") (pintype "passive"))
      (node (ref "R8") (pin "2") (pinfunction "2_2") (pintype "passive"))
      (node (ref "ZD1") (pin "A") (pinfunction "A_A") (pintype "passive"))
    )
    (net (code "51") (name "Net-(Q2-PadB)") (class "Default")
      (node (ref "Q2") (pin "B") (pinfunction "B_B") (pintype "passive"))
      (node (ref "R5") (pin "2") (pinfunction "2_2") (pintype "passive"))
    )
    (net (code "52") (name "Net-(Q3-PadB)") (class "Default")
      (node (ref "Q3") (pin "B") (pinfunction "B_B") (pintype "passive"))
      (node (ref "R4") (pin "1") (pinfunction "1_1") (pintype "passive"))
    )
    (net (code "53") (name "Net-(Q4-B)") (class "Default")
      (node (ref "D4") (pin "A") (pinfunction "A_A") (pintype "passive"))
      (node (ref "Q4") (pin "1") (pinfunction "B_1") (pintype "passive"))
      (node (ref "R12") (pin "2") (pinfunction "2_2") (pintype "passive"))
      (node (ref "R15") (pin "1") (pinfunction "1_1") (pintype "passive"))
    )
    (net (code "54") (name "Net-(Q4-E)") (class "Default")
      (node (ref "D1") (pin "A") (pinfunction "A_A") (pintype "passive"))
      (node (ref "Q4") (pin "3") (pinfunction "E_3") (pintype "passive"))
    )
    (net (code "55") (name "Net-(Q5-PadS)") (class "Default")
      (node (ref "Q5") (pin "S") (pinfunction "S_S") (pintype "passive"))
      (node (ref "R2") (pin "1") (pinfunction "1_1") (pintype "passive"))
      (node (ref "R5") (pin "1") (pinfunction "1_1") (pintype "passive"))
      (node (ref "R6") (pin "1") (pinfunction "1_1") (pintype "passive"))
    )
    (net (code "56") (name "Net-(Q6-E)") (class "Default")
      (node (ref "Q6") (pin "3") (pinfunction "E_3") (pintype "passive"))
      (node (ref "R14") (pin "1") (pinfunction "1_1") (pintype "passive"))
    )
    (net (code "57") (name "Net-(Q7-PadE)") (class "Default")
      (node (ref "Q7") (pin "E") (pinfunction "E_E") (pintype "passive"))
      (node (ref "R10") (pin "1") (pinfunction "1_1") (pintype "passive"))
    )
    (net (code "58") (name "Net-(Q8-PadC)") (class "Default")
      (node (ref "Q8") (pin "C") (pinfunction "C_C") (pintype "passive"))
      (node (ref "Q9") (pin "C") (pinfunction "C_C") (pintype "passive"))
      (node (ref "R15") (pin "2") (pinfunction "2_2") (pintype "passive"))
      (node (ref "R22") (pin "2") (pinfunction "2_2") (pintype "passive"))
    )
    (net (code "59") (name "Net-(Q8-PadE)") (class "Default")
      (node (ref "Q8") (pin "E") (pinfunction "E_E") (pintype "passive"))
      (node (ref "R11") (pin "1") (pinfunction "1_1") (pintype "passive"))
    )
    (net (code "60") (name "Net-(Q9-PadB)") (class "Default")
      (node (ref "Q9") (pin "B") (pinfunction "B_B") (pintype "passive"))
      (node (ref "R18") (pin "2") (pinfunction "2_2") (pintype "passive"))
      (node (ref "R8") (pin "1") (pinfunction "1_1") (pintype "passive"))
    )
    (net (code "61") (name "Net-(Q9-PadE)") (class "Default")
      (node (ref "Q9") (pin "E") (pinfunction "E_E") (pintype "passive"))
      (node (ref "R24") (pin "2") (pinfunction "2_2") (pintype "passive"))
    )
    (net (code "62") (name "Net-(Q10-PadC)") (class "Default")
      (node (ref "Q10") (pin "C") (pinfunction "C_C") (pintype "passive"))
      (node (ref "Q7") (pin "B") (pinfunction "B_B") (pintype "passive"))
      (node (ref "Q7") (pin "C") (pinfunction "C_C") (pintype "passive"))
      (node (ref "Q8") (pin "B") (pinfunction "B_B") (pintype "passive"))
    )
    (net (code "63") (name "Net-(Q10-PadE)") (class "Default")
      (node (ref "Q10") (pin "E") (pinfunction "E_E") (pintype "passive"))
      (node (ref "R27") (pin "2") (pinfunction "2_2") (pintype "passive"))
    )
    (net (code "64") (name "Net-(Q12-D)") (class "Default")
      (node (ref "Q12") (pin "3") (pinfunction "D_3") (pintype "passive"))
      (node (ref "R50") (pin "2") (pinfunction "2_2") (pintype "passive"))
      (node (ref "R52") (pin "2") (pinfunction "2_2") (pintype "passive"))
    )
    (net (code "65") (name "Net-(Q12-G)") (class "Default")
      (node (ref "D11") (pin "A") (pinfunction "A_A") (pintype "passive"))
      (node (ref "Q12") (pin "1") (pinfunction "G_1") (pintype "passive"))
      (node (ref "R49") (pin "2") (pinfunction "2_2") (pintype "passive"))
      (node (ref "X5") (pin "3") (pinfunction "S_3") (pintype "passive"))
    )
    (net (code "66") (name "Net-(Q13-D)") (class "Default")
      (node (ref "Q13") (pin "3") (pinfunction "D_3") (pintype "passive"))
      (node (ref "R58") (pin "2") (pinfunction "2_2") (pintype "passive"))
    )
    (net (code "67") (name "Net-(Q14-D)") (class "Default")
      (node (ref "Q14") (pin "3") (pinfunction "D_3") (pintype "passive"))
      (node (ref "R57") (pin "1") (pinfunction "1_1") (pintype "passive"))
    )
    (net (code "68") (name "Net-(R34-Pad2)") (class "Default")
      (node (ref "R34") (pin "2") (pinfunction "2_2") (pintype "passive"))
      (node (ref "R35") (pin "1") (pinfunction "1_1") (pintype "passive"))
    )
    (net (code "69") (name "Net-(R37-Pad1)") (class "Default")
      (node (ref "R37") (pin "1") (pinfunction "1_1") (pintype "passive"))
      (node (ref "R38") (pin "2") (pinfunction "2_2") (pintype "passive"))
    )
    (net (code "70") (name "Net-(R41-Pad1)") (class "Default")
      (node (ref "R41") (pin "1") (pinfunction "1_1") (pintype "passive"))
      (node (ref "R42") (pin "2") (pinfunction "2_2") (pintype "passive"))
    )
    (net (code "71") (name "Net-(R43-Pad1)") (class "Default")
      (node (ref "R43") (pin "1") (pinfunction "1_1") (pintype "passive"))
      (node (ref "R44") (pin "2") (pinfunction "2_2") (pintype "passive"))
    )
    (net (code "72") (name "Net-(X2F-KL)") (class "Default")
      (node (ref "C3") (pin "1") (pinfunction "1_1") (pintype "passive"))
      (node (ref "Q1") (pin "D") (pinfunction "D_D") (pintype "passive"))
      (node (ref "X2") (pin "14") (pinfunction "KL_14") (pintype "passive"))
      (node (ref "X2") (pin "15") (pinfunction "KL_15") (pintype "passive"))
      (node (ref "X2") (pin "16") (pinfunction "KL_16") (pintype "passive"))
      (node (ref "X2") (pin "17") (pinfunction "KL_17") (pintype "passive"))
    )
    (net (code "73") (name "Net-(X2J-KL)") (class "Default")
      (node (ref "C4") (pin "1") (pinfunction "1_1") (pintype "passive"))
      (node (ref "Q4") (pin "2") (pinfunction "C_2") (pintype "passive"))
      (node (ref "Q4") (pin "4") (pinfunction "C_4") (pintype "passive"))
      (node (ref "R10") (pin "2") (pinfunction "2_2") (pintype "passive"))
      (node (ref "R11") (pin "2") (pinfunction "2_2") (pintype "passive"))
      (node (ref "X2") (pin "18") (pinfunction "KL_18") (pintype "passive"))
    )
    (net (code "74") (name "Net-(X4B-S)") (class "Default")
      (node (ref "D10") (pin "C") (pinfunction "C_C") (pintype "passive"))
      (node (ref "X4") (pin "2") (pinfunction "S_2") (pintype "passive"))
    )
    (net (code "75") (name "Net-(X4D-S)") (class "Default")
      (node (ref "R47") (pin "1") (pinfunction "1_1") (pintype "passive"))
      (node (ref "X4") (pin "4") (pinfunction "S_4") (pintype "passive"))
    )
    (net (code "76") (name "Net-(X5A-S)") (class "Default")
      (node (ref "R52") (pin "1") (pinfunction "1_1") (pintype "passive"))
      (node (ref "X5") (pin "1") (pinfunction "S_1") (pintype "passive"))
    )
    (net (code "77") (name "Net-(X6A-S)") (class "Default")
      (node (ref "R57") (pin "2") (pinfunction "2_2") (pintype "passive"))
      (node (ref "X6") (pin "1") (pinfunction "S_1") (pintype "passive"))
    )
    (net (code "78") (name "Net-(X6C-S)") (class "Default")
      (node (ref "R58") (pin "1") (pinfunction "1_1") (pintype "passive"))
      (node (ref "X6") (pin "3") (pinfunction "S_3") (pintype "passive"))
    )
    (net (code "79") (name "OE_DRIVE") (class "Default")
      (node (ref "Q11") (pin "3") (pinfunction "D_3") (pintype "passive"))
      (node (ref "R27") (pin "1") (pinfunction "1_1") (pintype "passive"))
      (node (ref "R47") (pin "2") (pinfunction "2_2") (pintype "passive"))
    )
    (net (code "80") (name "OUT+") (class "Default")
      (node (ref "C1") (pin "1") (pinfunction "+_1") (pintype "passive"))
      (node (ref "C1") (pin "1.1") (pinfunction "+_1.1") (pintype "passive"))
      (node (ref "C11") (pin "1") (pinfunction "1_1") (pintype "passive"))
      (node (ref "C2") (pin "1") (pinfunction "1_1") (pintype "passive"))
      (node (ref "C24") (pin "1") (pinfunction "1_1") (pintype "passive"))
      (node (ref "C8") (pin "2") (pinfunction "2_2") (pintype "passive"))
      (node (ref "Q2") (pin "E") (pinfunction "E_E") (pintype "passive"))
      (node (ref "Q3") (pin "E") (pinfunction "E_E") (pintype "passive"))
      (node (ref "R1") (pin "1") (pinfunction "1_1") (pintype "passive"))
      (node (ref "R2") (pin "2") (pinfunction "2_2") (pintype "passive"))
      (node (ref "R9") (pin "1") (pinfunction "1_1") (pintype "passive"))
      (node (ref "X1") (pin "P$1") (pinfunction "1_P$1") (pintype "bidirectional"))
      (node (ref "X2") (pin "9") (pinfunction "KL_9") (pintype "passive"))
      (node (ref "ZD2") (pin "C") (pinfunction "1_C") (pintype "passive"))
    )
    (net (code "81") (name "OUT-") (class "Default")
      (node (ref "C1") (pin "2") (pinfunction "-_2") (pintype "passive"))
      (node (ref "C1") (pin "2.1") (pinfunction "-_2.1") (pintype "passive"))
      (node (ref "C7") (pin "1") (pinfunction "1_1") (pintype "passive"))
      (node (ref "C9") (pin "2") (pinfunction "2_2") (pintype "passive"))
      (node (ref "R32") (pin "2") (pinfunction "2_2") (pintype "passive"))
      (node (ref "R38") (pin "1") (pinfunction "1_1") (pintype "passive"))
      (node (ref "R40") (pin "1") (pinfunction "1_1") (pintype "passive"))
      (node (ref "R7") (pin "1") (pinfunction "1_1") (pintype "passive"))
      (node (ref "X1") (pin "P$2") (pinfunction "1_P$2") (pintype "bidirectional"))
      (node (ref "ZD2") (pin "A") (pinfunction "2_A") (pintype "passive"))
    )
    (net (code "82") (name "POUT-") (class "Default")
      (node (ref "R40") (pin "2") (pinfunction "2_2") (pintype "passive"))
      (node (ref "R42") (pin "1") (pinfunction "1_1") (pintype "passive"))
      (node (ref "SH1") (pin "2") (pinfunction "GND_B_2") (pintype "bidirectional"))
      (node (ref "X2") (pin "10") (pinfunction "KL_10") (pintype "passive"))
      (node (ref "X2") (pin "11") (pinfunction "KL_11") (pintype "passive"))
      (node (ref "X2") (pin "13") (pinfunction "KL_13") (pintype "passive"))
    )
    (net (code "83") (name "PREG_EN") (class "Default")
      (node (ref "D9") (pin "C") (pinfunction "C_C") (pintype "passive"))
      (node (ref "Q11") (pin "1") (pinfunction "G_1") (pintype "passive"))
      (node (ref "R48") (pin "2") (pinfunction "2_2") (pintype "passive"))
      (node (ref "X2") (pin "5") (pinfunction "KL_5") (pintype "passive"))
      (node (ref "X4") (pin "1") (pinfunction "S_1") (pintype "passive"))
    )
    (net (code "84") (name "PS_MISO") (class "Default")
      (node (ref "IC5") (pin "3") (pinfunction "SO_3") (pintype "output"))
      (node (ref "IC8") (pin "15") (pinfunction "DOUT/~{DRDY}_15") (pintype "output"))
      (node (ref "X7") (pin "9") (pinfunction "KL_9") (pintype "passive"))
    )
    (net (code "85") (name "PS_MOSI") (class "Default")
      (node (ref "IC5") (pin "2") (pinfunction "SI_2") (pintype "input"))
      (node (ref "IC6") (pin "7") (pinfunction "DIN_7") (pintype "input"))
      (node (ref "IC8") (pin "16") (pinfunction "DIN_16") (pintype "input"))
      (node (ref "X7") (pin "1") (pinfunction "KL_1") (pintype "passive"))
    )
    (net (code "86") (name "PS_SCLK") (class "Default")
      (node (ref "IC5") (pin "1") (pinfunction "SCK_1") (pintype "input"))
      (node (ref "IC6") (pin "6") (pinfunction "SCLK_6") (pintype "input"))
      (node (ref "IC8") (pin "1") (pinfunction "SCLK_1") (pintype "input"))
      (node (ref "X7") (pin "7") (pinfunction "KL_7") (pintype "passive"))
    )
    (net (code "87") (name "PWRGOOD") (class "Default")
      (node (ref "D10") (pin "A") (pinfunction "A_A") (pintype "passive"))
      (node (ref "IC5") (pin "16") (pinfunction "GP6_16") (pintype "bidirectional"))
      (node (ref "X2") (pin "1") (pinfunction "KL_1") (pintype "passive"))
    )
    (net (code "88") (name "SENSE+") (class "Default")
      (node (ref "C6") (pin "1") (pinfunction "1_1") (pintype "passive"))
      (node (ref "R21") (pin "2") (pinfunction "2_2") (pintype "passive"))
      (node (ref "R9") (pin "2") (pinfunction "2_2") (pintype "passive"))
      (node (ref "X1") (pin "P$3") (pinfunction "1_P$3") (pintype "bidirectional"))
    )
    (net (code "89") (name "SENSE-") (class "Default")
      (node (ref "C12") (pin "1") (pinfunction "1_1") (pintype "passive"))
      (node (ref "R31") (pin "2") (pinfunction "2_2") (pintype "passive"))
      (node (ref "R32") (pin "1") (pinfunction "1_1") (pintype "passive"))
      (node (ref "X1") (pin "P$4") (pinfunction "1_P$4") (pintype "bidirectional"))
    )
    (net (code "90") (name "SET_OE") (class "Default")
      (node (ref "D9") (pin "A") (pinfunction "A_A") (pintype "passive"))
      (node (ref "IC5") (pin "17") (pinfunction "GP7_17") (pintype "bidirectional"))
    )
    (net (code "91") (name "TEMP_FREQ") (class "Default")
      (node (ref "IC5") (pin "13") (pinfunction "GP3_13") (pintype "bidirectional"))
      (node (ref "X2") (pin "3") (pinfunction "KL_3") (pintype "passive"))
    )
    (net (code "92") (name "U_MON") (class "Default")
      (node (ref "IC1") (pin "7") (pinfunction "OUT_7") (pintype "output"))
      (node (ref "IC8") (pin "10") (pinfunction "AIN1_10") (pintype "input"))
      (node (ref "R25") (pin "1") (pinfunction "1_1") (pintype "passive"))
      (node (ref "R26") (pin "1") (pinfunction "1_1") (pintype "passive"))
    )
    (net (code "93") (name "U_SERVO") (class "Default")
      (node (ref "D5") (pin "C") (pinfunction "C_C") (pintype "passive"))
      (node (ref "D6") (pin "A") (pinfunction "A_A") (pintype "passive"))
      (node (ref "IC1") (pin "1") (pinfunction "OUT_1") (pintype "output"))
      (node (ref "R28") (pin "2") (pinfunction "2_2") (pintype "passive"))
      (node (ref "R51") (pin "1") (pinfunction "1_1") (pintype "passive"))
    )
    (net (code "94") (name "U_SET") (class "Default")
      (node (ref "R23") (pin "1") (pinfunction "1_1") (pintype "passive"))
      (node (ref "X3") (pin "3") (pinfunction "1_3") (pintype "passive"))
    )
    (net (code "95") (name "U_SET_IN") (class "Default")
      (node (ref "IC6") (pin "4") (pinfunction "VOUTA_4") (pintype "output"))
      (node (ref "IC8") (pin "11") (pinfunction "AIN0/REFP1_11") (pintype "input"))
      (node (ref "X3") (pin "1") (pinfunction "1_1") (pintype "passive"))
    )
    (net (code "96") (name "V+") (class "Default")
      (node (ref "C13") (pin "2") (pinfunction "2_2") (pintype "passive"))
      (node (ref "C14") (pin "1") (pinfunction "1_1") (pintype "passive"))
      (node (ref "C15") (pin "2") (pinfunction "2_2") (pintype "passive"))
      (node (ref "C16") (pin "2") (pinfunction "2_2") (pintype "passive"))
      (node (ref "C17") (pin "2") (pinfunction "2_2") (pintype "passive"))
      (node (ref "C25") (pin "2") (pinfunction "2_2") (pintype "passive"))
      (node (ref "IC1") (pin "8") (pinfunction "V+_8") (pintype "power_in"))
      (node (ref "IC2") (pin "8") (pinfunction "V+_8") (pintype "power_in"))
      (node (ref "IC3") (pin "7") (pinfunction "V+_7") (pintype "power_in"))
      (node (ref "IC4") (pin "3") (pinfunction "V+_3") (pintype "power_in"))
      (node (ref "R54") (pin "2") (pinfunction "2_2") (pintype "passive"))
      (node (ref "X2") (pin "6") (pinfunction "KL_6") (pintype "passive"))
    )
    (net (code "97") (name "V-") (class "Default")
      (node (ref "C18") (pin "2") (pinfunction "2_2") (pintype "passive"))
      (node (ref "C19") (pin "2") (pinfunction "2_2") (pintype "passive"))
      (node (ref "C20") (pin "1") (pinfunction "1_1") (pintype "passive"))
      (node (ref "C21") (pin "2") (pinfunction "2_2") (pintype "passive"))
      (node (ref "C22") (pin "2") (pinfunction "2_2") (pintype "passive"))
      (node (ref "C26") (pin "2") (pinfunction "2_2") (pintype "passive"))
      (node (ref "IC1") (pin "4") (pinfunction "V-_4") (pintype "power_in"))
      (node (ref "IC2") (pin "4") (pinfunction "V-_4") (pintype "power_in"))
      (node (ref "IC3") (pin "4") (pinfunction "V-_4") (pintype "power_in"))
      (node (ref "IC4") (pin "12") (pinfunction "GND_12") (pintype "power_in"))
      (node (ref "R61") (pin "1") (pinfunction "1_1") (pintype "passive"))
      (node (ref "X2") (pin "4") (pinfunction "KL_4") (pintype "passive"))
    )
    (net (code "98") (name "unconnected-(IC7-TEMP-Pad3)") (class "Default")
      (node (ref "IC7") (pin "3") (pinfunction "TEMP_3") (pintype "input"))
    )
    (net (code "99") (name "~{CC_ACTIVE}") (class "Default")
      (node (ref "IC5") (pin "12") (pinfunction "GP2_12") (pintype "bidirectional"))
      (node (ref "Q14") (pin "1") (pinfunction "G_1") (pintype "passive"))
      (node (ref "R60") (pin "1") (pinfunction "1_1") (pintype "passive"))
      (node (ref "R62") (pin "2") (pinfunction "2_2") (pintype "passive"))
    )
    (net (code "100") (name "~{CV_ACTIVE}") (class "Default")
      (node (ref "IC5") (pin "15") (pinfunction "GP5_15") (pintype "bidirectional"))
      (node (ref "Q13") (pin "1") (pinfunction "G_1") (pintype "passive"))
      (node (ref "R53") (pin "1") (pinfunction "1_1") (pintype "passive"))
      (node (ref "R55") (pin "2") (pinfunction "2_2") (pintype "passive"))
    )
    (net (code "101") (name "~{DP_DRIVE}") (class "Default")
      (node (ref "Q6") (pin "1") (pinfunction "B_1") (pintype "passive"))
      (node (ref "R13") (pin "1") (pinfunction "1_1") (pintype "passive"))
      (node (ref "R50") (pin "1") (pinfunction "1_1") (pintype "passive"))
    )
    (net (code "102") (name "~{INT}") (class "Default")
      (node (ref "JP1") (pin "3") (pinfunction "3_3") (pintype "passive"))
      (node (ref "X7") (pin "8") (pinfunction "KL_8") (pintype "passive"))
    )
    (net (code "103") (name "~{PS_DRDY}") (class "Default")
      (node (ref "IC8") (pin "14") (pinfunction "~{DRDY}_14") (pintype "output"))
      (node (ref "JP1") (pin "2") (pinfunction "2_2") (pintype "passive"))
    )
    (net (code "104") (name "~{PS_RESET}") (class "Default")
      (node (ref "IC5") (pin "6") (pinfunction "~{RESET}_6") (pintype "input"))
      (node (ref "X7") (pin "5") (pinfunction "KL_5") (pintype "passive"))
    )
    (net (code "105") (name "~{SET_DP}") (class "Default")
      (node (ref "D11") (pin "C") (pinfunction "C_C") (pintype "passive"))
      (node (ref "IC5") (pin "11") (pinfunction "GP1_11") (pintype "bidirectional"))
    )
  )
)
